# seven_buttons.net
KiCad netlist of a schematic drawn in EAGLE
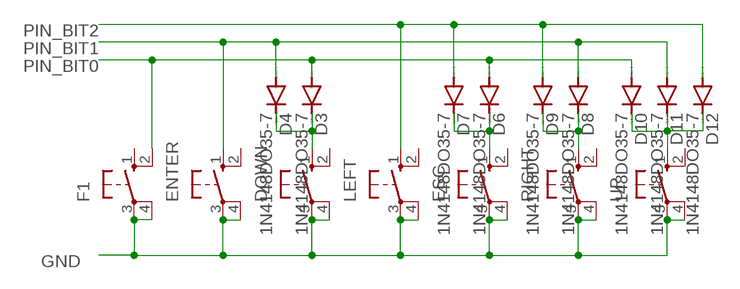
[diagram p0: schematic, sheet 1]

(export (version "E")
  (design (tool "Eeschema 10.0.6"))
  (components
    (comp (ref "D3")
      (value "1N4148DO35-7")
      (footprint "eagle-import:DO35-7")
      (libsource (lib "eagle-import") (part "1N4148DO35-7"))
    )
    (comp (ref "D4")
      (value "1N4148DO35-7")
      (footprint "eagle-import:DO35-7")
      (libsource (lib "eagle-import") (part "1N4148DO35-7"))
    )
    (comp (ref "D6")
      (value "1N4148DO35-7")
      (footprint "eagle-import:DO35-7")
      (libsource (lib "eagle-import") (part "1N4148DO35-7"))
    )
    (comp (ref "D7")
      (value "1N4148DO35-7")
      (footprint "eagle-import:DO35-7")
      (libsource (lib "eagle-import") (part "1N4148DO35-7"))
    )
    (comp (ref "D8")
      (value "1N4148DO35-7")
      (footprint "eagle-import:DO35-7")
      (libsource (lib "eagle-import") (part "1N4148DO35-7"))
    )
    (comp (ref "D9")
      (value "1N4148DO35-7")
      (footprint "eagle-import:DO35-7")
      (libsource (lib "eagle-import") (part "1N4148DO35-7"))
    )
    (comp (ref "D10")
      (value "1N4148DO35-7")
      (footprint "eagle-import:DO35-7")
      (libsource (lib "eagle-import") (part "1N4148DO35-7"))
    )
    (comp (ref "D11")
      (value "1N4148DO35-7")
      (footprint "eagle-import:DO35-7")
      (libsource (lib "eagle-import") (part "1N4148DO35-7"))
    )
    (comp (ref "D12")
      (value "1N4148DO35-7")
      (footprint "eagle-import:DO35-7")
      (libsource (lib "eagle-import") (part "1N4148DO35-7"))
    )
    (comp (ref "DOWN")
      (value "10-XX")
      (footprint "eagle-import:B3F-10XX")
      (fields (field (name "MPN") "B3F-1000"))
      (libsource (lib "eagle-import") (part "10-XX"))
    )
    (comp (ref "ENTER")
      (value "10-XX")
      (footprint "eagle-import:B3F-10XX")
      (fields (field (name "MPN") "B3F-1000"))
      (libsource (lib "eagle-import") (part "10-XX"))
    )
    (comp (ref "ESC")
      (value "10-XX")
      (footprint "eagle-import:B3F-10XX")
      (fields (field (name "MPN") "B3F-1000"))
      (libsource (lib "eagle-import") (part "10-XX"))
    )
    (comp (ref "F1")
      (value "10-XX")
      (footprint "eagle-import:B3F-10XX")
      (fields (field (name "MPN") "B3F-1000"))
      (libsource (lib "eagle-import") (part "10-XX"))
    )
    (comp (ref "LEFT")
      (value "10-XX")
      (footprint "eagle-import:B3F-10XX")
      (fields (field (name "MPN") "B3F-1000"))
      (libsource (lib "eagle-import") (part "10-XX"))
    )
    (comp (ref "RIGHT")
      (value "10-XX")
      (footprint "eagle-import:B3F-10XX")
      (fields (field (name "MPN") "B3F-1000"))
      (libsource (lib "eagle-import") (part "10-XX"))
    )
    (comp (ref "UP")
      (value "10-XX")
      (footprint "eagle-import:B3F-10XX")
      (fields (field (name "MPN") "B3F-1000"))
      (libsource (lib "eagle-import") (part "10-XX"))
    )
  )
  (nets
    (net (code "1") (name "/GND") (class "Default")
      (node (ref "DOWN") (pin "3") (pinfunction "P_3") (pintype "passive"))
      (node (ref "DOWN") (pin "4") (pinfunction "P1_4") (pintype "passive"))
      (node (ref "ENTER") (pin "3") (pinfunction "P_3") (pintype "passive"))
      (node (ref "ENTER") (pin "4") (pinfunction "P1_4") (pintype "passive"))
      (node (ref "ESC") (pin "3") (pinfunction "P_3") (pintype "passive"))
      (node (ref "ESC") (pin "4") (pinfunction "P1_4") (pintype "passive"))
      (node (ref "F1") (pin "3") (pinfunction "P_3") (pintype "passive"))
      (node (ref "F1") (pin "4") (pinfunction "P1_4") (pintype "passive"))
      (node (ref "LEFT") (pin "3") (pinfunction "P_3") (pintype "passive"))
      (node (ref "LEFT") (pin "4") (pinfunction "P1_4") (pintype "passive"))
      (node (ref "RIGHT") (pin "3") (pinfunction "P_3") (pintype "passive"))
      (node (ref "RIGHT") (pin "4") (pinfunction "P1_4") (pintype "passive"))
      (node (ref "UP") (pin "3") (pinfunction "P_3") (pintype "passive"))
      (node (ref "UP") (pin "4") (pinfunction "P1_4") (pintype "passive"))
    )
    (net (code "2") (name "/PIN_BIT0") (class "Default")
      (node (ref "D10") (pin "A") (pinfunction "A_A") (pintype "passive"))
      (node (ref "D3") (pin "A") (pinfunction "A_A") (pintype "passive"))
      (node (ref "D6") (pin "A") (pinfunction "A_A") (pintype "passive"))
      (node (ref "F1") (pin "2") (pinfunction "S1_2") (pintype "passive"))
    )
    (net (code "3") (name "/PIN_BIT1") (class "Default")
      (node (ref "D11") (pin "A") (pinfunction "A_A") (pintype "passive"))
      (node (ref "D4") (pin "A") (pinfunction "A_A") (pintype "passive"))
      (node (ref "D8") (pin "A") (pinfunction "A_A") (pintype "passive"))
      (node (ref "ENTER") (pin "1") (pinfunction "S_1") (pintype "passive"))
    )
    (net (code "4") (name "/PIN_BIT2") (class "Default")
      (node (ref "D12") (pin "A") (pinfunction "A_A") (pintype "passive"))
      (node (ref "D7") (pin "A") (pinfunction "A_A") (pintype "passive"))
      (node (ref "D9") (pin "A") (pinfunction "A_A") (pintype "passive"))
      (node (ref "LEFT") (pin "1") (pinfunction "S_1") (pintype "passive"))
    )
    (net (code "5") (name "Net-(DOWN-S)") (class "Default")
      (node (ref "D3") (pin "C") (pinfunction "C_C") (pintype "passive"))
      (node (ref "D4") (pin "C") (pinfunction "C_C") (pintype "passive"))
      (node (ref "DOWN") (pin "1") (pinfunction "S_1") (pintype "passive"))
    )
    (net (code "6") (name "Net-(ESC-S)") (class "Default")
      (node (ref "D6") (pin "C") (pinfunction "C_C") (pintype "passive"))
      (node (ref "D7") (pin "C") (pinfunction "C_C") (pintype "passive"))
      (node (ref "ESC") (pin "1") (pinfunction "S_1") (pintype "passive"))
    )
    (net (code "7") (name "Net-(RIGHT-S)") (class "Default")
      (node (ref "D8") (pin "C") (pinfunction "C_C") (pintype "passive"))
      (node (ref "D9") (pin "C") (pinfunction "C_C") (pintype "passive"))
      (node (ref "RIGHT") (pin "1") (pinfunction "S_1") (pintype "passive"))
    )
    (net (code "8") (name "Net-(UP-S)") (class "Default")
      (node (ref "D10") (pin "C") (pinfunction "C_C") (pintype "passive"))
      (node (ref "D11") (pin "C") (pinfunction "C_C") (pintype "passive"))
      (node (ref "D12") (pin "C") (pinfunction "C_C") (pintype "passive"))
      (node (ref "UP") (pin "1") (pinfunction "S_1") (pintype "passive"))
    )
    (net (code "9") (name "unconnected-(DOWN-S1-Pad2)") (class "Default")
      (node (ref "DOWN") (pin "2") (pinfunction "S1_2") (pintype "passive"))
    )
    (net (code "10") (name "unconnected-(ENTER-S1-Pad2)") (class "Default")
      (node (ref "ENTER") (pin "2") (pinfunction "S1_2") (pintype "passive"))
    )
    (net (code "11") (name "unconnected-(ESC-S1-Pad2)") (class "Default")
      (node (ref "ESC") (pin "2") (pinfunction "S1_2") (pintype "passive"))
    )
    (net (code "12") (name "unconnected-(F1-S-Pad1)") (class "Default")
      (node (ref "F1") (pin "1") (pinfunction "S_1") (pintype "passive"))
    )
    (net (code "13") (name "unconnected-(LEFT-S1-Pad2)") (class "Default")
      (node (ref "LEFT") (pin "2") (pinfunction "S1_2") (pintype "passive"))
    )
    (net (code "14") (name "unconnected-(RIGHT-S1-Pad2)") (class "Default")
      (node (ref "RIGHT") (pin "2") (pinfunction "S1_2") (pintype "passive"))
    )
    (net (code "15") (name "unconnected-(UP-S1-Pad2)") (class "Default")
      (node (ref "UP") (pin "2") (pinfunction "S1_2") (pintype "passive"))
    )
  )
)
